# POWER.net
KiCad netlist of a schematic drawn in Altium Designer
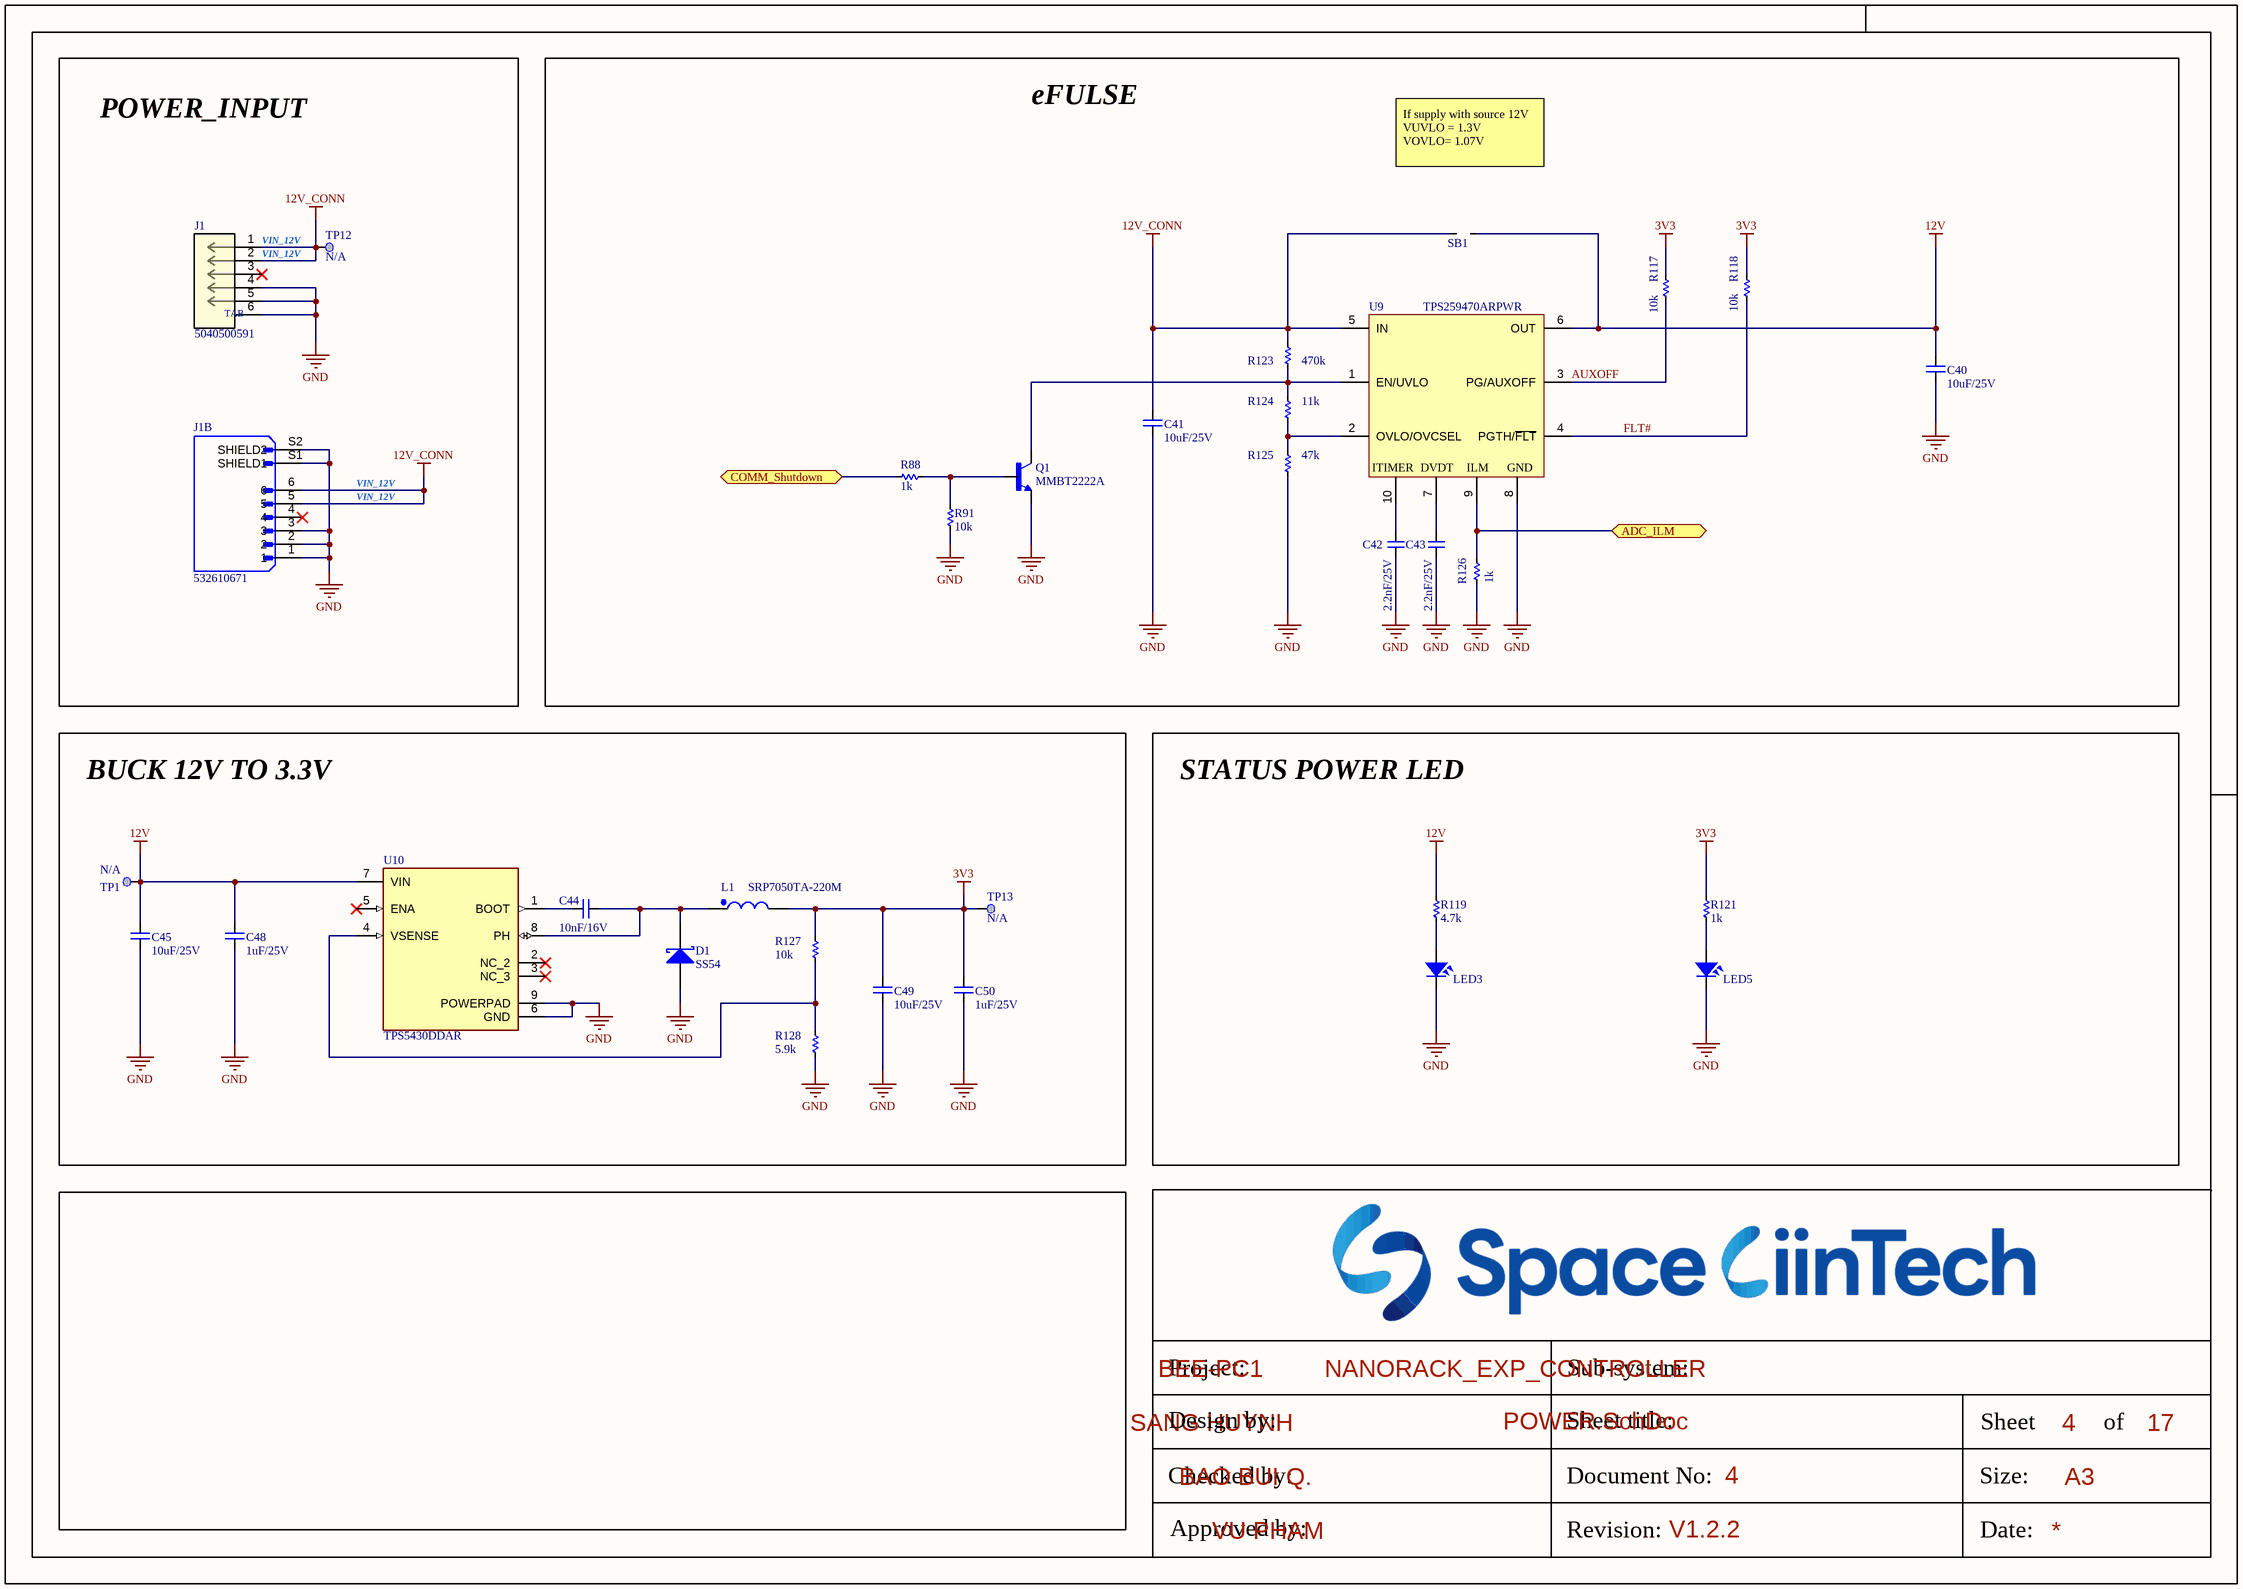
[diagram p0: POWER.SchDoc]

(export (version "E")
  (design (tool "Eeschema 10.0.6"))
  (components
    (comp (ref "C40")
      (value "10uF/25V")
      (footprint "CAP_C_1608X80")
      (description "CAP_Chip")
      (libsource (lib "LABLIB") (part "CAP_SMD"))
    )
    (comp (ref "C41")
      (value "10uF/25V")
      (footprint "CAP_C_1608X80")
      (description "CAP_Chip")
      (libsource (lib "LABLIB") (part "CAP_SMD"))
    )
    (comp (ref "C42")
      (value "2.2nF/25V")
      (footprint "CAP_C_1608X80")
      (description "CAP CHIP")
      (libsource (lib "LABLIB") (part "_CAP_C_2"))
    )
    (comp (ref "C43")
      (value "2.2nF/25V")
      (footprint "CAP_C_1608X80")
      (description "CAP CHIP")
      (libsource (lib "LABLIB") (part "_CAP_C_2"))
    )
    (comp (ref "C44")
      (value "10nF/16V")
      (footprint "CAP_C_1608X80")
      (description "CAP_Chip")
      (libsource (lib "LABLIB") (part "CAP_SMD"))
    )
    (comp (ref "C45")
      (value "10uF/25V")
      (footprint "CAP_C_1608X80")
      (description "CAP_Chip")
      (libsource (lib "LABLIB") (part "CAP_SMD"))
    )
    (comp (ref "C48")
      (value "1uF/25V")
      (footprint "CAP_C_1608X80")
      (description "CAP_Chip")
      (libsource (lib "LABLIB") (part "CAP_SMD"))
    )
    (comp (ref "C49")
      (value "10uF/25V")
      (footprint "CAP_C_1608X80")
      (description "CAP_Chip")
      (libsource (lib "LABLIB") (part "CAP_SMD"))
    )
    (comp (ref "C50")
      (value "1uF/25V")
      (footprint "CAP_C_1608X80")
      (description "CAP_Chip")
      (libsource (lib "LABLIB") (part "CAP_SMD"))
    )
    (comp (ref "D1")
      (value "SS54")
      (footprint "DO-214AC_SMA")
      (description "DIODE SCHOTTKY 40V 5A SMA")
      (fields (field (name "MPN") "SS34"))
      (libsource (lib "COMM_SCHLIB") (part "SS54"))
    )
    (comp (ref "J1")
      (value "5040500591")
      (footprint "5040500591")
      (fields (field (name "COPYRIGHT") "Copyright (C) 2025 Ultra Librarian. All rights reserved."))
      (libsource (lib "COMM_SCHLIB") (part "5040500591"))
    )
    (comp (ref "J1B")
      (value "532610671")
      (footprint "MOLEX_532610671")
      (libsource (lib "COMM_SCHLIB") (part "CONN_SMD_06"))
    )
    (comp (ref "L1")
      (value "SRP7050TA-220M")
      (footprint "SRP7050TA-220M")
      (description "FIXED IND 22UH 2.5A 170 MOHM SMD")
      (libsource (lib "LABLIB") (part "_IND"))
    )
    (comp (ref "LED3")
      (value "150060RS75000")
      (footprint "LED_0603")
      (libsource (lib "COMM_SCHLIB") (part "LED SMD"))
    )
    (comp (ref "LED5")
      (value "150060YS75000")
      (footprint "LED_0603")
      (libsource (lib "COMM_SCHLIB") (part "LED SMD"))
    )
    (comp (ref "Q1")
      (value "MMBT2222A")
      (footprint "SOT95P240X120-3N")
      (description "BJT, SOT-23, 40V, 600mA, NPN, 0.25W, 150Â°C")
      (fields (field (name "MF") "Diotec Semiconductor"))
      (libsource (lib "COMM_SCHLIB") (part "MMBT2222A"))
    )
    (comp (ref "R88")
      (value "1k")
      (footprint "RES_C_1608X60")
      (description "RES")
      (libsource (lib "LABLIB") (part "_RES_B_2"))
    )
    (comp (ref "R91")
      (value "10k")
      (footprint "RES_C_1608X60")
      (description "RES")
      (libsource (lib "LABLIB") (part "_RES_B_2"))
    )
    (comp (ref "R117")
      (value "10k")
      (footprint "RES_C_1608X60")
      (description "RES")
      (libsource (lib "LABLIB") (part "_RES_B_2"))
    )
    (comp (ref "R118")
      (value "10k")
      (footprint "RES_C_1608X60")
      (description "RES")
      (libsource (lib "LABLIB") (part "_RES_B_2"))
    )
    (comp (ref "R119")
      (value "4.7k")
      (footprint "RES_C_1608X60")
      (description "RES")
      (libsource (lib "LABLIB") (part "_RES_B_2"))
    )
    (comp (ref "R121")
      (value "1k")
      (footprint "RES_C_1608X60")
      (description "RES")
      (libsource (lib "LABLIB") (part "_RES_B_2"))
    )
    (comp (ref "R123")
      (value "470k")
      (footprint "RES_C_1608X60")
      (description "RES")
      (libsource (lib "LABLIB") (part "_RES_B_2"))
    )
    (comp (ref "R124")
      (value "11k")
      (footprint "RES_C_1608X60")
      (description "RES")
      (libsource (lib "LABLIB") (part "_RES_B_2"))
    )
    (comp (ref "R125")
      (value "47k")
      (footprint "RES_C_1608X60")
      (description "RES")
      (libsource (lib "LABLIB") (part "_RES_B_2"))
    )
    (comp (ref "R126")
      (value "1k")
      (footprint "RES_C_1608X60")
      (description "RES")
      (libsource (lib "LABLIB") (part "_RES_B_2"))
    )
    (comp (ref "R127")
      (value "10k")
      (footprint "RES_C_1608X60")
      (description "RES")
      (libsource (lib "LABLIB") (part "_RES_B_2"))
    )
    (comp (ref "R128")
      (value "5.9k")
      (footprint "RES_C_1608X60")
      (description "RES")
      (libsource (lib "LABLIB") (part "_RES_B_2"))
    )
    (comp (ref "SB1")
      (value "JUMPER")
      (footprint "JUMPER_1608")
      (libsource (lib "COMM_SCHLIB") (part "JUMPER"))
    )
    (comp (ref "TP1")
      (value "N/A")
      (footprint "TESTPOINT")
      (description "Test Point 0.3mm")
      (fields (field (name "INTERNAL_PART_NUMBER") "MCD-00630") (field (name "Comment") "Test Point"))
      (libsource (lib "") (part "Test Point_1"))
    )
    (comp (ref "TP12")
      (value "N/A")
      (footprint "TESTPOINT")
      (description "Test Point 0.3mm")
      (fields (field (name "INTERNAL_PART_NUMBER") "MCD-00630") (field (name "Comment") "Test Point"))
      (libsource (lib "MCD_PARTS_database") (part "Test Point"))
    )
    (comp (ref "TP13")
      (value "N/A")
      (footprint "TESTPOINT")
      (description "Test Point 0.3mm")
      (fields (field (name "INTERNAL_PART_NUMBER") "MCD-00630") (field (name "Comment") "Test Point"))
      (libsource (lib "MCD_PARTS_database") (part "Test Point"))
    )
    (comp (ref "U9")
      (value "TPS259470ARPWR")
      (footprint "VQFN-HR-10")
      (libsource (lib "COMM_SCHLIB") (part "TPS259470ARPWR"))
    )
    (comp (ref "U10")
      (value "TPS5430DDAR")
      (footprint "CONV_TPS5430DDAR")
      (description "5.5V to 36V Input, 3A, 500kHz Step-Down Converter")
      (fields (field (name "MF") "Texas Instruments"))
      (libsource (lib "COMM_SCHLIB") (part "TPS5430DDAR"))
    )
  )
  (nets
    (net (code "1") (name "/ADC_ILM") (class "Default")
      (node (ref "R126") (pin "1") (pinfunction "1_1") (pintype "passive"))
      (node (ref "U9") (pin "9") (pinfunction "ILM_9") (pintype "passive"))
    )
    (net (code "2") (name "/AUXOFF") (class "Default")
      (node (ref "R117") (pin "1") (pinfunction "1_1") (pintype "passive"))
      (node (ref "U9") (pin "3") (pinfunction "PG/AUXOFF_3") (pintype "passive"))
    )
    (net (code "3") (name "/COMM_Shutdown") (class "Default")
      (node (ref "R88") (pin "1") (pinfunction "1_1") (pintype "passive"))
    )
    (net (code "4") (name "/FLT#") (class "Default")
      (node (ref "R118") (pin "1") (pinfunction "1_1") (pintype "passive"))
      (node (ref "U9") (pin "4") (pinfunction "PGTH/~{FLT}_4") (pintype "passive"))
    )
    (net (code "5") (name "3V3") (class "Default")
      (node (ref "C49") (pin "2") (pinfunction "2_2") (pintype "passive"))
      (node (ref "C50") (pin "2") (pinfunction "2_2") (pintype "passive"))
      (node (ref "L1") (pin "2") (pinfunction "2_2") (pintype "passive"))
      (node (ref "R117") (pin "2") (pinfunction "2_2") (pintype "passive"))
      (node (ref "R118") (pin "2") (pinfunction "2_2") (pintype "passive"))
      (node (ref "R121") (pin "2") (pinfunction "2_2") (pintype "passive"))
      (node (ref "R127") (pin "1") (pinfunction "1_1") (pintype "passive"))
      (node (ref "TP13") (pin "1") (pinfunction "1_1") (pintype "passive"))
    )
    (net (code "6") (name "12V") (class "Default")
      (node (ref "C40") (pin "2") (pinfunction "2_2") (pintype "passive"))
      (node (ref "C45") (pin "2") (pinfunction "2_2") (pintype "passive"))
      (node (ref "C48") (pin "2") (pinfunction "2_2") (pintype "passive"))
      (node (ref "R119") (pin "2") (pinfunction "2_2") (pintype "passive"))
      (node (ref "SB1") (pin "2") (pinfunction "2_2") (pintype "passive"))
      (node (ref "TP1") (pin "1") (pinfunction "1_1") (pintype "passive"))
      (node (ref "U10") (pin "7") (pinfunction "VIN_7") (pintype "power_in"))
      (node (ref "U9") (pin "6") (pinfunction "OUT_6") (pintype "passive"))
    )
    (net (code "7") (name "12V_CONN") (class "Default")
      (node (ref "C41") (pin "2") (pinfunction "2_2") (pintype "passive"))
      (node (ref "J1") (pin "1") (pinfunction "1_1") (pintype "passive"))
      (node (ref "J1") (pin "2") (pinfunction "2_2") (pintype "passive"))
      (node (ref "J1B") (pin "5") (pinfunction "5_5") (pintype "passive"))
      (node (ref "J1B") (pin "6") (pinfunction "6_6") (pintype "passive"))
      (node (ref "R123") (pin "1") (pinfunction "1_1") (pintype "passive"))
      (node (ref "SB1") (pin "1") (pinfunction "1_1") (pintype "passive"))
      (node (ref "TP12") (pin "1") (pinfunction "1_1") (pintype "passive"))
      (node (ref "U9") (pin "5") (pinfunction "IN_5") (pintype "passive"))
    )
    (net (code "8") (name "GND") (class "Default")
      (node (ref "C40") (pin "1") (pinfunction "1_1") (pintype "passive"))
      (node (ref "C41") (pin "1") (pinfunction "1_1") (pintype "passive"))
      (node (ref "C42") (pin "1") (pinfunction "1_1") (pintype "passive"))
      (node (ref "C43") (pin "1") (pinfunction "1_1") (pintype "passive"))
      (node (ref "C45") (pin "1") (pinfunction "1_1") (pintype "passive"))
      (node (ref "C48") (pin "1") (pinfunction "1_1") (pintype "passive"))
      (node (ref "C49") (pin "1") (pinfunction "1_1") (pintype "passive"))
      (node (ref "C50") (pin "1") (pinfunction "1_1") (pintype "passive"))
      (node (ref "D1") (pin "1") (pinfunction "A_1") (pintype "passive"))
      (node (ref "J1") (pin "4") (pinfunction "4_4") (pintype "passive"))
      (node (ref "J1") (pin "5") (pinfunction "5_5") (pintype "passive"))
      (node (ref "J1") (pin "6") (pinfunction "6_6") (pintype "passive"))
      (node (ref "J1B") (pin "1") (pinfunction "1_1") (pintype "passive"))
      (node (ref "J1B") (pin "2") (pinfunction "2_2") (pintype "passive"))
      (node (ref "J1B") (pin "3") (pinfunction "3_3") (pintype "passive"))
      (node (ref "J1B") (pin "S1") (pinfunction "SHIELD1_S1") (pintype "passive"))
      (node (ref "J1B") (pin "S2") (pinfunction "SHIELD2_S2") (pintype "passive"))
      (node (ref "LED3") (pin "2") (pinfunction "2_2") (pintype "passive"))
      (node (ref "LED5") (pin "2") (pinfunction "2_2") (pintype "passive"))
      (node (ref "Q1") (pin "2") (pinfunction "E_2") (pintype "passive"))
      (node (ref "R125") (pin "2") (pinfunction "2_2") (pintype "passive"))
      (node (ref "R126") (pin "2") (pinfunction "2_2") (pintype "passive"))
      (node (ref "R128") (pin "2") (pinfunction "2_2") (pintype "passive"))
      (node (ref "R91") (pin "1") (pinfunction "1_1") (pintype "passive"))
      (node (ref "U10") (pin "6") (pinfunction "GND_6") (pintype "power_in"))
      (node (ref "U10") (pin "9") (pinfunction "POWERPAD_9") (pintype "power_in"))
      (node (ref "U9") (pin "8") (pinfunction "GND_8") (pintype "passive"))
    )
    (net (code "9") (name "Net-(D1-K)") (class "Default")
      (node (ref "C44") (pin "1") (pinfunction "1_1") (pintype "passive"))
      (node (ref "D1") (pin "2") (pinfunction "K_2") (pintype "passive"))
      (node (ref "L1") (pin "1") (pinfunction "1_1") (pintype "passive"))
      (node (ref "U10") (pin "8") (pinfunction "PH_8") (pintype "bidirectional"))
    )
    (net (code "10") (name "Net-(LED3-Pad1)") (class "Default")
      (node (ref "LED3") (pin "1") (pinfunction "1_1") (pintype "passive"))
      (node (ref "R119") (pin "1") (pinfunction "1_1") (pintype "passive"))
    )
    (net (code "11") (name "Net-(LED5-Pad1)") (class "Default")
      (node (ref "LED5") (pin "1") (pinfunction "1_1") (pintype "passive"))
      (node (ref "R121") (pin "1") (pinfunction "1_1") (pintype "passive"))
    )
    (net (code "12") (name "Net-(Q1-B)") (class "Default")
      (node (ref "Q1") (pin "1") (pinfunction "B_1") (pintype "passive"))
      (node (ref "R88") (pin "2") (pinfunction "2_2") (pintype "passive"))
      (node (ref "R91") (pin "2") (pinfunction "2_2") (pintype "passive"))
    )
    (net (code "13") (name "Net-(Q1-C)") (class "Default")
      (node (ref "Q1") (pin "3") (pinfunction "C_3") (pintype "passive"))
      (node (ref "R123") (pin "2") (pinfunction "2_2") (pintype "passive"))
      (node (ref "R124") (pin "1") (pinfunction "1_1") (pintype "passive"))
      (node (ref "U9") (pin "1") (pinfunction "EN/UVLO_1") (pintype "passive"))
    )
    (net (code "14") (name "Net-(U9-DVDT)") (class "Default")
      (node (ref "C43") (pin "2") (pinfunction "2_2") (pintype "passive"))
      (node (ref "U9") (pin "7") (pinfunction "DVDT_7") (pintype "passive"))
    )
    (net (code "15") (name "Net-(U9-ITIMER)") (class "Default")
      (node (ref "C42") (pin "2") (pinfunction "2_2") (pintype "passive"))
      (node (ref "U9") (pin "10") (pinfunction "ITIMER_10") (pintype "passive"))
    )
    (net (code "16") (name "Net-(U9-OVLO{slash}OVCSEL)") (class "Default")
      (node (ref "R124") (pin "2") (pinfunction "2_2") (pintype "passive"))
      (node (ref "R125") (pin "1") (pinfunction "1_1") (pintype "passive"))
      (node (ref "U9") (pin "2") (pinfunction "OVLO/OVCSEL_2") (pintype "passive"))
    )
    (net (code "17") (name "Net-(U10-BOOT)") (class "Default")
      (node (ref "C44") (pin "2") (pinfunction "2_2") (pintype "passive"))
      (node (ref "U10") (pin "1") (pinfunction "BOOT_1") (pintype "output"))
    )
    (net (code "18") (name "Net-(U10-VSENSE)") (class "Default")
      (node (ref "R127") (pin "2") (pinfunction "2_2") (pintype "passive"))
      (node (ref "R128") (pin "1") (pinfunction "1_1") (pintype "passive"))
      (node (ref "U10") (pin "4") (pinfunction "VSENSE_4") (pintype "input"))
    )
    (net (code "19") (name "unconnected-(J1-Pad3)") (class "Default")
      (node (ref "J1") (pin "3") (pinfunction "3_3") (pintype "passive+no_connect"))
    )
    (net (code "20") (name "unconnected-(J1B-Pad4)") (class "Default")
      (node (ref "J1B") (pin "4") (pinfunction "4_4") (pintype "passive+no_connect"))
    )
    (net (code "21") (name "unconnected-(U10-ENA-Pad5)") (class "Default")
      (node (ref "U10") (pin "5") (pinfunction "ENA_5") (pintype "input+no_connect"))
    )
    (net (code "22") (name "unconnected-(U10-NC_2-Pad2)") (class "Default")
      (node (ref "U10") (pin "2") (pinfunction "NC_2_2") (pintype "passive+no_connect"))
    )
    (net (code "23") (name "unconnected-(U10-NC_3-Pad3)") (class "Default")
      (node (ref "U10") (pin "3") (pinfunction "NC_3_3") (pintype "passive+no_connect"))
    )
  )
)
